# SAM_D21_DevBoard.net
KiCad netlist of a schematic drawn in EAGLE
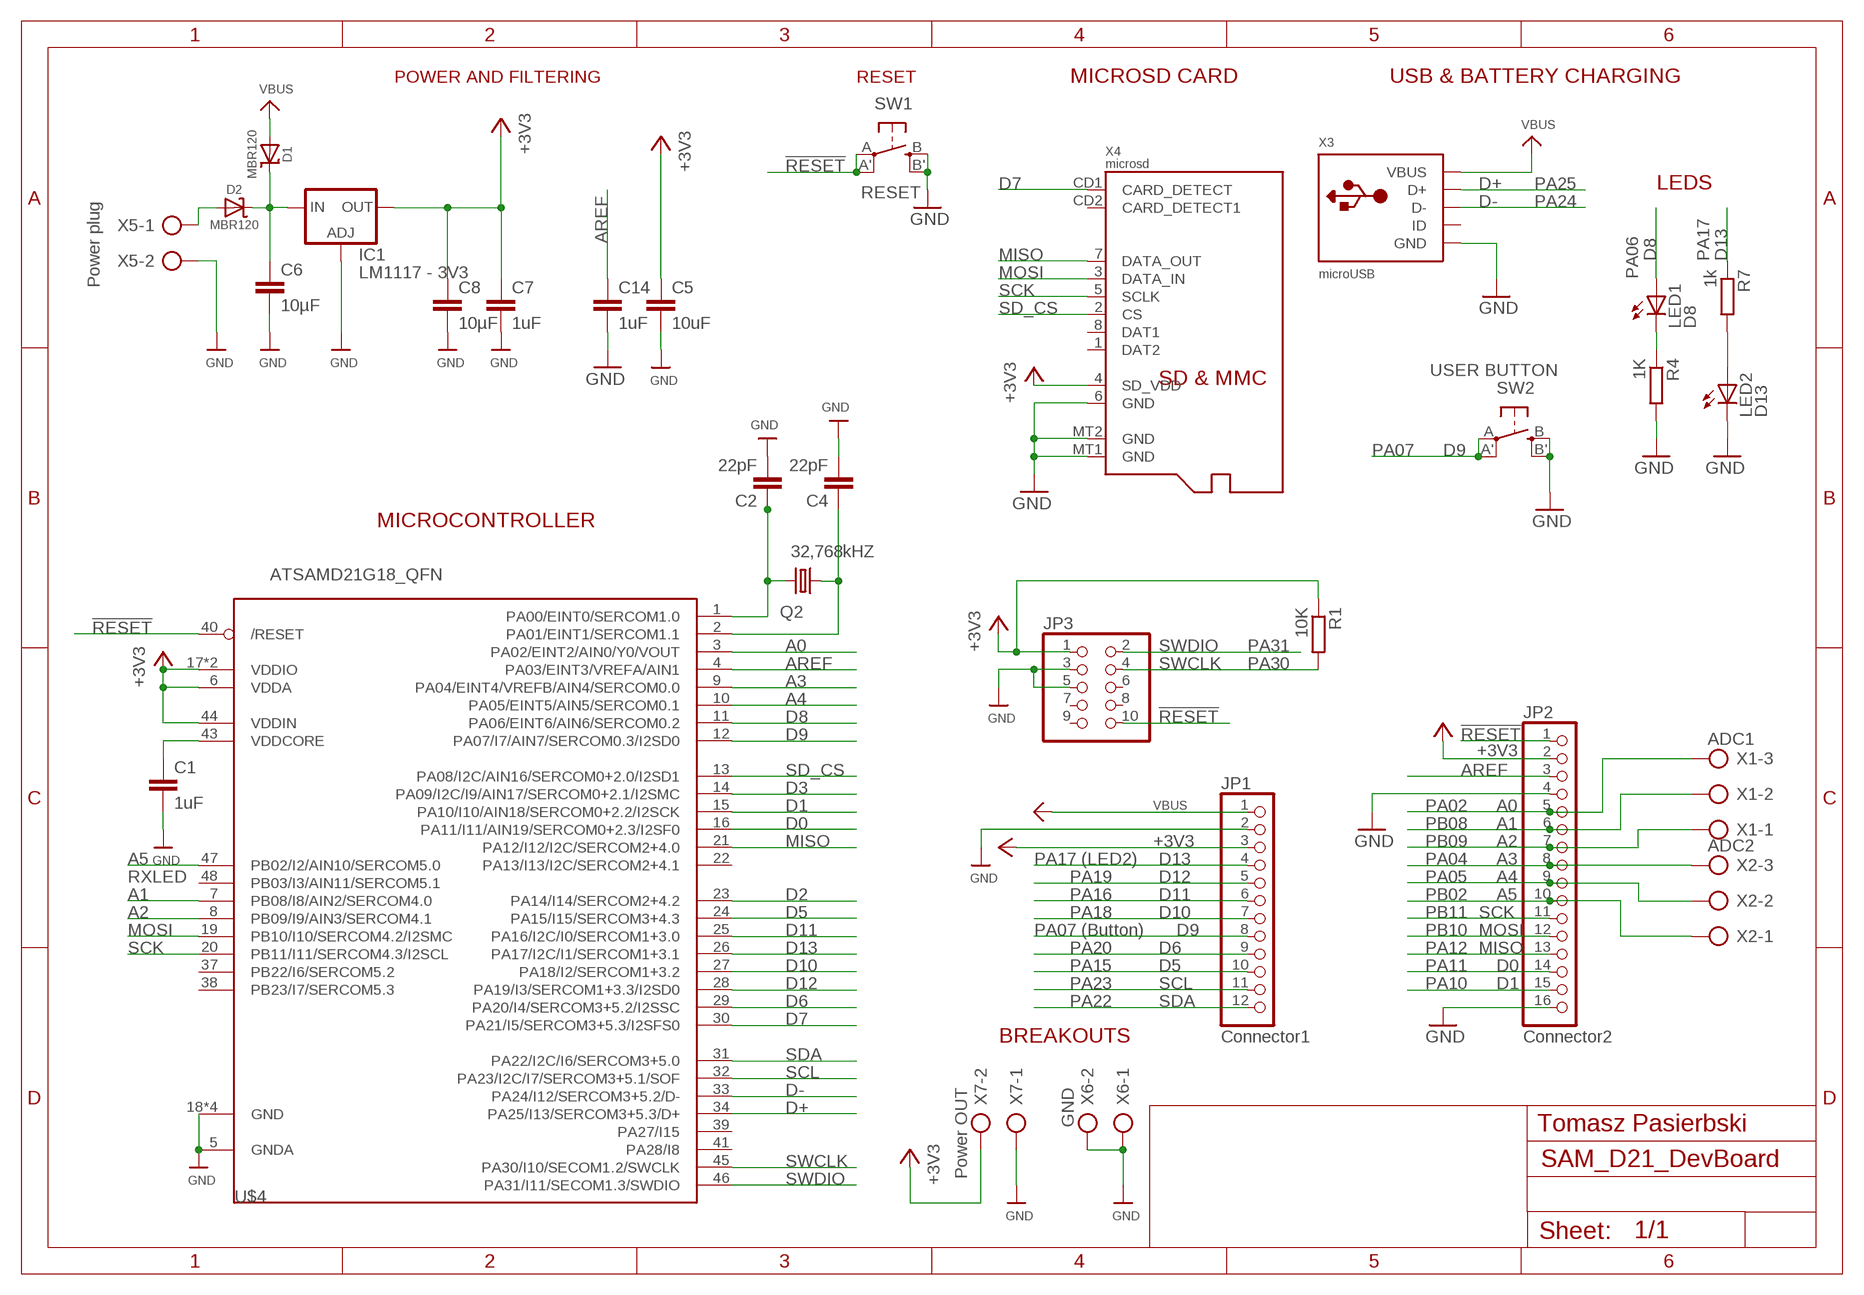
[diagram p0: schematic, sheet 1]

(export (version "E")
  (design (tool "Eeschema 10.0.6"))
  (components
    (comp (ref "C1")
      (value "1uF")
      (footprint "eagle-import:C1206")
      (libsource (lib "eagle-import") (part "C-EUC1206"))
    )
    (comp (ref "C2")
      (value "22pF")
      (footprint "eagle-import:C1206")
      (libsource (lib "eagle-import") (part "C-EUC1206"))
    )
    (comp (ref "C4")
      (value "22pF")
      (footprint "eagle-import:C1206")
      (libsource (lib "eagle-import") (part "C-EUC1206"))
    )
    (comp (ref "C5")
      (value "10uF")
      (footprint "eagle-import:C1206")
      (libsource (lib "eagle-import") (part "C-EUC1206"))
    )
    (comp (ref "C6")
      (value "10µF")
      (footprint "eagle-import:C1206")
      (libsource (lib "eagle-import") (part "C-EUC1206"))
    )
    (comp (ref "C7")
      (value "1uF")
      (footprint "eagle-import:C1206")
      (libsource (lib "eagle-import") (part "C-EUC1206"))
    )
    (comp (ref "C8")
      (value "10µF")
      (footprint "eagle-import:C1206")
      (libsource (lib "eagle-import") (part "C-EUC1206"))
    )
    (comp (ref "C14")
      (value "1uF")
      (footprint "eagle-import:C1206")
      (libsource (lib "eagle-import") (part "C-EUC1206"))
    )
    (comp (ref "D1")
      (value "MBR120")
      (footprint "eagle-import:SOD-123")
      (libsource (lib "eagle-import") (part "DIODE-SCHOTTKYSOD-123"))
    )
    (comp (ref "D2")
      (value "MBR120")
      (footprint "eagle-import:SOD-123")
      (libsource (lib "eagle-import") (part "DIODE-SCHOTTKYSOD-123"))
    )
    (comp (ref "IC1")
      (value "LM1117 - 3V3")
      (footprint "eagle-import:SOT223")
      (libsource (lib "eagle-import") (part "LD117A?S33TR"))
    )
    (comp (ref "JP1")
      (value "Connector1")
      (footprint "eagle-import:1X12")
      (libsource (lib "eagle-import") (part "PINHD-1X12"))
    )
    (comp (ref "JP2")
      (value "Connector2")
      (footprint "eagle-import:1X16")
      (libsource (lib "eagle-import") (part "PINHD-1X16"))
    )
    (comp (ref "JP3")
      (value "PINHD-2X5")
      (footprint "eagle-import:2X05")
      (libsource (lib "eagle-import") (part "PINHD-2X5"))
    )
    (comp (ref "LED1")
      (value "D8")
      (footprint "eagle-import:1206")
      (libsource (lib "eagle-import") (part "LEDSMT1206"))
    )
    (comp (ref "LED2")
      (value "D13")
      (footprint "eagle-import:1206")
      (libsource (lib "eagle-import") (part "LEDSMT1206"))
    )
    (comp (ref "Q2")
      (value "32,768kHZ")
      (footprint "eagle-import:HC49UP")
      (libsource (lib "eagle-import") (part "CRYSTALHC49UP"))
    )
    (comp (ref "R1")
      (value "10K")
      (footprint "eagle-import:M1206")
      (libsource (lib "eagle-import") (part "R-EU_M1206"))
    )
    (comp (ref "R4")
      (value "1K")
      (footprint "eagle-import:M1206")
      (libsource (lib "eagle-import") (part "R-EU_M1206"))
    )
    (comp (ref "R7")
      (value "1k")
      (footprint "eagle-import:M1206")
      (libsource (lib "eagle-import") (part "R-EU_M1206"))
    )
    (comp (ref "SW1")
      (value "RESET")
      (footprint "eagle-import:EVQ-Q2")
      (libsource (lib "eagle-import") (part "SPST_TACT-EVQQ2"))
    )
    (comp (ref "SW2")
      (value "USER BUTTON")
      (footprint "eagle-import:EVQ-Q2")
      (libsource (lib "eagle-import") (part "SPST_TACT-EVQQ2"))
    )
    (comp (ref "U$4")
      (value "ATSAMD21G18_QFN")
      (footprint "eagle-import:TQFN48_7MM")
      (libsource (lib "eagle-import") (part "ATSAMD21J_QFN"))
    )
    (comp (ref "X1")
      (value "ADC1")
      (footprint "eagle-import:AK300_3")
      (libsource (lib "eagle-import") (part "AK300/3"))
    )
    (comp (ref "X2")
      (value "ADC2")
      (footprint "eagle-import:AK300_3")
      (libsource (lib "eagle-import") (part "AK300/3"))
    )
    (comp (ref "X3")
      (value "microUSB")
      (footprint "eagle-import:4UCONN_20329_V2")
      (libsource (lib "eagle-import") (part "USB_MICRO_20329_V2"))
    )
    (comp (ref "X4")
      (value "microsd")
      (footprint "eagle-import:MICROSD")
      (libsource (lib "eagle-import") (part "MICROSD"))
    )
    (comp (ref "X5")
      (value "Power plug")
      (footprint "eagle-import:AK300_2")
      (libsource (lib "eagle-import") (part "AK300/2"))
    )
    (comp (ref "X6")
      (value "GND")
      (footprint "eagle-import:AK300_2")
      (libsource (lib "eagle-import") (part "AK300/2"))
    )
    (comp (ref "X7")
      (value "Power OUT")
      (footprint "eagle-import:AK300_2")
      (libsource (lib "eagle-import") (part "AK300/2"))
    )
  )
  (nets
    (net (code "1") (name "+3V3") (class "Default")
      (node (ref "C5") (pin "1") (pinfunction "1_1") (pintype "passive"))
      (node (ref "C7") (pin "1") (pinfunction "1_1") (pintype "passive"))
      (node (ref "C8") (pin "1") (pinfunction "1_1") (pintype "passive"))
      (node (ref "IC1") (pin "4") (pinfunction "OUT_4") (pintype "passive"))
      (node (ref "JP1") (pin "3") (pinfunction "3_3") (pintype "passive"))
      (node (ref "JP2") (pin "2") (pinfunction "2_2") (pintype "passive"))
      (node (ref "JP3") (pin "1") (pinfunction "1_1") (pintype "passive"))
      (node (ref "R1") (pin "1") (pinfunction "1_1") (pintype "passive"))
      (node (ref "U$4") (pin "17") (pinfunction "VDDIO_17") (pintype "power_in"))
      (node (ref "U$4") (pin "36") (pinfunction "VDDIO_36") (pintype "power_in"))
      (node (ref "U$4") (pin "44") (pinfunction "VDDIN_44") (pintype "power_in"))
      (node (ref "U$4") (pin "6") (pinfunction "VDDA_6") (pintype "power_in"))
      (node (ref "X4") (pin "4") (pinfunction "SD_VDD_4") (pintype "power_in"))
      (node (ref "X7") (pin "2") (pinfunction "KL_2") (pintype "passive"))
    )
    (net (code "2") (name "/A0") (class "Default")
      (node (ref "JP2") (pin "5") (pinfunction "5_5") (pintype "passive"))
      (node (ref "U$4") (pin "3") (pinfunction "PA02/EINT2/AIN0/Y0/VOUT_3") (pintype "bidirectional"))
      (node (ref "X1") (pin "3") (pinfunction "KL_3") (pintype "passive"))
    )
    (net (code "3") (name "/A1") (class "Default")
      (node (ref "JP2") (pin "6") (pinfunction "6_6") (pintype "passive"))
      (node (ref "U$4") (pin "7") (pinfunction "PB08/I8/AIN2/SERCOM4.0_7") (pintype "bidirectional"))
      (node (ref "X1") (pin "2") (pinfunction "KL_2") (pintype "passive"))
    )
    (net (code "4") (name "/A2") (class "Default")
      (node (ref "JP2") (pin "7") (pinfunction "7_7") (pintype "passive"))
      (node (ref "U$4") (pin "8") (pinfunction "PB09/I9/AIN3/SERCOM4.1_8") (pintype "bidirectional"))
      (node (ref "X1") (pin "1") (pinfunction "KL_1") (pintype "passive"))
    )
    (net (code "5") (name "/A3") (class "Default")
      (node (ref "JP2") (pin "8") (pinfunction "8_8") (pintype "passive"))
      (node (ref "U$4") (pin "9") (pinfunction "PA04/EINT4/VREFB/AIN4/SERCOM0.0_9") (pintype "bidirectional"))
      (node (ref "X2") (pin "3") (pinfunction "KL_3") (pintype "passive"))
    )
    (net (code "6") (name "/A4") (class "Default")
      (node (ref "JP2") (pin "9") (pinfunction "9_9") (pintype "passive"))
      (node (ref "U$4") (pin "10") (pinfunction "PA05/EINT5/AIN5/SERCOM0.1_10") (pintype "bidirectional"))
      (node (ref "X2") (pin "2") (pinfunction "KL_2") (pintype "passive"))
    )
    (net (code "7") (name "/A5") (class "Default")
      (node (ref "JP2") (pin "10") (pinfunction "10_10") (pintype "passive"))
      (node (ref "U$4") (pin "47") (pinfunction "PB02/I2/AIN10/SERCOM5.0_47") (pintype "bidirectional"))
      (node (ref "X2") (pin "1") (pinfunction "KL_1") (pintype "passive"))
    )
    (net (code "8") (name "/AREF") (class "Default")
      (node (ref "C14") (pin "1") (pinfunction "1_1") (pintype "passive"))
      (node (ref "JP2") (pin "3") (pinfunction "3_3") (pintype "passive"))
      (node (ref "U$4") (pin "4") (pinfunction "PA03/EINT3/VREFA/AIN1_4") (pintype "bidirectional"))
    )
    (net (code "9") (name "/D+") (class "Default")
      (node (ref "U$4") (pin "34") (pinfunction "PA25/I13/SERCOM3+5.3/D+_34") (pintype "bidirectional"))
      (node (ref "X3") (pin "D+") (pinfunction "D+_D+") (pintype "bidirectional"))
    )
    (net (code "10") (name "/D-") (class "Default")
      (node (ref "U$4") (pin "33") (pinfunction "PA24/I12/SERCOM3+5.2/D-_33") (pintype "bidirectional"))
      (node (ref "X3") (pin "D-") (pinfunction "D-_D-") (pintype "bidirectional"))
    )
    (net (code "11") (name "/D0") (class "Default")
      (node (ref "JP2") (pin "14") (pinfunction "14_14") (pintype "passive"))
      (node (ref "U$4") (pin "16") (pinfunction "PA11/I11/AIN19/SERCOM0+2.3/I2SF0_16") (pintype "bidirectional"))
    )
    (net (code "12") (name "/D1") (class "Default")
      (node (ref "JP2") (pin "15") (pinfunction "15_15") (pintype "passive"))
      (node (ref "U$4") (pin "15") (pinfunction "PA10/I10/AIN18/SERCOM0+2.2/I2SCK_15") (pintype "bidirectional"))
    )
    (net (code "13") (name "/D2") (class "Default")
      (node (ref "U$4") (pin "23") (pinfunction "PA14/I14/SERCOM2+4.2_23") (pintype "bidirectional"))
    )
    (net (code "14") (name "/D3") (class "Default")
      (node (ref "U$4") (pin "14") (pinfunction "PA09/I2C/I9/AIN17/SERCOM0+2.1/I2SMC_14") (pintype "bidirectional"))
    )
    (net (code "15") (name "/D5") (class "Default")
      (node (ref "JP1") (pin "10") (pinfunction "10_10") (pintype "passive"))
      (node (ref "U$4") (pin "24") (pinfunction "PA15/I15/SERCOM3+4.3_24") (pintype "bidirectional"))
    )
    (net (code "16") (name "/D6") (class "Default")
      (node (ref "JP1") (pin "9") (pinfunction "9_9") (pintype "passive"))
      (node (ref "U$4") (pin "29") (pinfunction "PA20/I4/SERCOM3+5.2/I2SSC_29") (pintype "bidirectional"))
    )
    (net (code "17") (name "/D7") (class "Default")
      (node (ref "U$4") (pin "30") (pinfunction "PA21/I5/SERCOM3+5.3/I2SFS0_30") (pintype "bidirectional"))
      (node (ref "X4") (pin "CD1") (pinfunction "CARD_DETECT_CD1") (pintype "passive"))
    )
    (net (code "18") (name "/D8") (class "Default")
      (node (ref "LED1") (pin "A") (pinfunction "A_A") (pintype "passive"))
      (node (ref "U$4") (pin "11") (pinfunction "PA06/EINT6/AIN6/SERCOM0.2_11") (pintype "bidirectional"))
    )
    (net (code "19") (name "/D9") (class "Default")
      (node (ref "JP1") (pin "8") (pinfunction "8_8") (pintype "passive"))
      (node (ref "SW2") (pin "A") (pinfunction "P_A") (pintype "passive"))
      (node (ref "SW2") (pin "A'") (pinfunction "P1_A'") (pintype "passive"))
      (node (ref "U$4") (pin "12") (pinfunction "PA07/I7/AIN7/SERCOM0.3/I2SD0_12") (pintype "bidirectional"))
    )
    (net (code "20") (name "/D10") (class "Default")
      (node (ref "JP1") (pin "7") (pinfunction "7_7") (pintype "passive"))
      (node (ref "U$4") (pin "27") (pinfunction "PA18/I2/SERCOM1+3.2_27") (pintype "bidirectional"))
    )
    (net (code "21") (name "/D11") (class "Default")
      (node (ref "JP1") (pin "6") (pinfunction "6_6") (pintype "passive"))
      (node (ref "U$4") (pin "25") (pinfunction "PA16/I2C/I0/SERCOM1+3.0_25") (pintype "bidirectional"))
    )
    (net (code "22") (name "/D12") (class "Default")
      (node (ref "JP1") (pin "5") (pinfunction "5_5") (pintype "passive"))
      (node (ref "U$4") (pin "28") (pinfunction "PA19/I3/SERCOM1+3.3/I2SD0_28") (pintype "bidirectional"))
    )
    (net (code "23") (name "/D13") (class "Default")
      (node (ref "JP1") (pin "4") (pinfunction "4_4") (pintype "passive"))
      (node (ref "R7") (pin "1") (pinfunction "1_1") (pintype "passive"))
      (node (ref "U$4") (pin "26") (pinfunction "PA17/I2C/I1/SERCOM1+3.1_26") (pintype "bidirectional"))
    )
    (net (code "24") (name "/MISO") (class "Default")
      (node (ref "JP2") (pin "13") (pinfunction "13_13") (pintype "passive"))
      (node (ref "U$4") (pin "21") (pinfunction "PA12/I12/I2C/SERCOM2+4.0_21") (pintype "bidirectional"))
      (node (ref "X4") (pin "7") (pinfunction "DATA_OUT_7") (pintype "output"))
    )
    (net (code "25") (name "/MOSI") (class "Default")
      (node (ref "JP2") (pin "12") (pinfunction "12_12") (pintype "passive"))
      (node (ref "U$4") (pin "19") (pinfunction "PB10/I10/SERCOM4.2/I2SMC_19") (pintype "bidirectional"))
      (node (ref "X4") (pin "3") (pinfunction "DATA_IN_3") (pintype "input"))
    )
    (net (code "26") (name "/SCK") (class "Default")
      (node (ref "JP2") (pin "11") (pinfunction "11_11") (pintype "passive"))
      (node (ref "U$4") (pin "20") (pinfunction "PB11/I11/SERCOM4.3/I2SCL_20") (pintype "bidirectional"))
      (node (ref "X4") (pin "5") (pinfunction "SCLK_5") (pintype "input"))
    )
    (net (code "27") (name "/SCL") (class "Default")
      (node (ref "JP1") (pin "11") (pinfunction "11_11") (pintype "passive"))
      (node (ref "U$4") (pin "32") (pinfunction "PA23/I2C/I7/SERCOM3+5.1/SOF_32") (pintype "bidirectional"))
    )
    (net (code "28") (name "/SDA") (class "Default")
      (node (ref "JP1") (pin "12") (pinfunction "12_12") (pintype "passive"))
      (node (ref "U$4") (pin "31") (pinfunction "PA22/I2C/I6/SERCOM3+5.0_31") (pintype "bidirectional"))
    )
    (net (code "29") (name "/SD_CS") (class "Default")
      (node (ref "U$4") (pin "13") (pinfunction "PA08/I2C/AIN16/SERCOM0+2.0/I2SD1_13") (pintype "bidirectional"))
      (node (ref "X4") (pin "2") (pinfunction "CS_2") (pintype "input"))
    )
    (net (code "30") (name "/SWCLK") (class "Default")
      (node (ref "JP3") (pin "4") (pinfunction "4_4") (pintype "passive"))
      (node (ref "R1") (pin "2") (pinfunction "2_2") (pintype "passive"))
      (node (ref "U$4") (pin "45") (pinfunction "PA30/I10/SECOM1.2/SWCLK_45") (pintype "bidirectional"))
    )
    (net (code "31") (name "/SWDIO") (class "Default")
      (node (ref "JP3") (pin "2") (pinfunction "2_2") (pintype "passive"))
      (node (ref "U$4") (pin "46") (pinfunction "PA31/I11/SECOM1.3/SWDIO_46") (pintype "bidirectional"))
    )
    (net (code "32") (name "/~{RESET}") (class "Default")
      (node (ref "JP2") (pin "1") (pinfunction "1_1") (pintype "passive"))
      (node (ref "JP3") (pin "10") (pinfunction "10_10") (pintype "passive"))
      (node (ref "SW1") (pin "A") (pinfunction "P_A") (pintype "passive"))
      (node (ref "SW1") (pin "A'") (pinfunction "P1_A'") (pintype "passive"))
      (node (ref "U$4") (pin "40") (pinfunction "/RESET_40") (pintype "bidirectional"))
    )
    (net (code "33") (name "GND") (class "Default")
      (node (ref "C1") (pin "2") (pinfunction "2_2") (pintype "passive"))
      (node (ref "C14") (pin "2") (pinfunction "2_2") (pintype "passive"))
      (node (ref "C2") (pin "2") (pinfunction "2_2") (pintype "passive"))
      (node (ref "C4") (pin "2") (pinfunction "2_2") (pintype "passive"))
      (node (ref "C5") (pin "2") (pinfunction "2_2") (pintype "passive"))
      (node (ref "C6") (pin "2") (pinfunction "2_2") (pintype "passive"))
      (node (ref "C7") (pin "2") (pinfunction "2_2") (pintype "passive"))
      (node (ref "C8") (pin "2") (pinfunction "2_2") (pintype "passive"))
      (node (ref "IC1") (pin "1") (pinfunction "ADJ_1") (pintype "input"))
      (node (ref "JP1") (pin "2") (pinfunction "2_2") (pintype "passive"))
      (node (ref "JP2") (pin "16") (pinfunction "16_16") (pintype "passive"))
      (node (ref "JP2") (pin "4") (pinfunction "4_4") (pintype "passive"))
      (node (ref "JP3") (pin "3") (pinfunction "3_3") (pintype "passive"))
      (node (ref "JP3") (pin "5") (pinfunction "5_5") (pintype "passive"))
      (node (ref "LED2") (pin "C") (pinfunction "C_C") (pintype "passive"))
      (node (ref "R4") (pin "2") (pinfunction "2_2") (pintype "passive"))
      (node (ref "SW1") (pin "B") (pinfunction "S_B") (pintype "passive"))
      (node (ref "SW1") (pin "B'") (pinfunction "S1_B'") (pintype "passive"))
      (node (ref "SW2") (pin "B") (pinfunction "S_B") (pintype "passive"))
      (node (ref "SW2") (pin "B'") (pinfunction "S1_B'") (pintype "passive"))
      (node (ref "U$4") (pin "18") (pinfunction "GND_18") (pintype "power_in"))
      (node (ref "U$4") (pin "35") (pinfunction "GND_35") (pintype "power_in"))
      (node (ref "U$4") (pin "42") (pinfunction "GND_42") (pintype "power_in"))
      (node (ref "U$4") (pin "5") (pinfunction "GNDA_5") (pintype "power_in"))
      (node (ref "U$4") (pin "THERMAL") (pinfunction "GND_THERMAL") (pintype "power_in"))
      (node (ref "X3") (pin "BASE@1") (pinfunction "GND_BASE@1") (pintype "power_in"))
      (node (ref "X3") (pin "BASE@2") (pinfunction "GND_BASE@2") (pintype "power_in"))
      (node (ref "X3") (pin "GND") (pinfunction "GND_GND") (pintype "power_in"))
      (node (ref "X3") (pin "SPRT@1") (pinfunction "GND_SPRT@1") (pintype "power_in"))
      (node (ref "X3") (pin "SPRT@2") (pinfunction "GND_SPRT@2") (pintype "power_in"))
      (node (ref "X3") (pin "SPRT@3") (pinfunction "GND_SPRT@3") (pintype "power_in"))
      (node (ref "X3") (pin "SPRT@4") (pinfunction "GND_SPRT@4") (pintype "power_in"))
      (node (ref "X4") (pin "6") (pinfunction "GND_6") (pintype "power_in"))
      (node (ref "X4") (pin "MT1") (pinfunction "GND_MT1") (pintype "power_in"))
      (node (ref "X4") (pin "MT2") (pinfunction "GND_MT2") (pintype "power_in"))
      (node (ref "X5") (pin "2") (pinfunction "KL_2") (pintype "passive"))
      (node (ref "X6") (pin "1") (pinfunction "KL_1") (pintype "passive"))
      (node (ref "X6") (pin "2") (pinfunction "KL_2") (pintype "passive"))
      (node (ref "X7") (pin "1") (pinfunction "KL_1") (pintype "passive"))
    )
    (net (code "34") (name "Net-(IC1-IN)") (class "Default")
      (node (ref "C6") (pin "1") (pinfunction "1_1") (pintype "passive"))
      (node (ref "D1") (pin "C") (pinfunction "C_C") (pintype "passive"))
      (node (ref "D2") (pin "C") (pinfunction "C_C") (pintype "passive"))
      (node (ref "IC1") (pin "3") (pinfunction "IN_3") (pintype "input"))
    )
    (net (code "35") (name "Net-(LED1-PadC)") (class "Default")
      (node (ref "LED1") (pin "C") (pinfunction "C_C") (pintype "passive"))
      (node (ref "R4") (pin "1") (pinfunction "1_1") (pintype "passive"))
    )
    (net (code "36") (name "Net-(LED2-PadA)") (class "Default")
      (node (ref "LED2") (pin "A") (pinfunction "A_A") (pintype "passive"))
      (node (ref "R7") (pin "2") (pinfunction "2_2") (pintype "passive"))
    )
    (net (code "37") (name "Net-(U$4-PA00{slash}EINT0{slash}SERCOM1.0)") (class "Default")
      (node (ref "C2") (pin "1") (pinfunction "1_1") (pintype "passive"))
      (node (ref "Q2") (pin "2") (pinfunction "2_2") (pintype "passive"))
      (node (ref "U$4") (pin "1") (pinfunction "PA00/EINT0/SERCOM1.0_1") (pintype "bidirectional"))
    )
    (net (code "38") (name "Net-(U$4-PA01{slash}EINT1{slash}SERCOM1.1)") (class "Default")
      (node (ref "C4") (pin "1") (pinfunction "1_1") (pintype "passive"))
      (node (ref "Q2") (pin "1") (pinfunction "1_1") (pintype "passive"))
      (node (ref "U$4") (pin "2") (pinfunction "PA01/EINT1/SERCOM1.1_2") (pintype "bidirectional"))
    )
    (net (code "39") (name "Net-(U$4-VDDCORE)") (class "Default")
      (node (ref "C1") (pin "1") (pinfunction "1_1") (pintype "passive"))
      (node (ref "U$4") (pin "43") (pinfunction "VDDCORE_43") (pintype "power_in"))
    )
    (net (code "40") (name "Net-(X5A-KL)") (class "Default")
      (node (ref "D2") (pin "A") (pinfunction "A_A") (pintype "passive"))
      (node (ref "X5") (pin "1") (pinfunction "KL_1") (pintype "passive"))
    )
    (net (code "41") (name "VBUS") (class "Default")
      (node (ref "D1") (pin "A") (pinfunction "A_A") (pintype "passive"))
      (node (ref "JP1") (pin "1") (pinfunction "1_1") (pintype "passive"))
      (node (ref "X3") (pin "VBUS") (pinfunction "VBUS_VBUS") (pintype "power_in"))
    )
    (net (code "42") (name "unconnected-(JP3-Pad6)") (class "Default")
      (node (ref "JP3") (pin "6") (pinfunction "6_6") (pintype "passive"))
    )
    (net (code "43") (name "unconnected-(JP3-Pad7)") (class "Default")
      (node (ref "JP3") (pin "7") (pinfunction "7_7") (pintype "passive"))
    )
    (net (code "44") (name "unconnected-(JP3-Pad8)") (class "Default")
      (node (ref "JP3") (pin "8") (pinfunction "8_8") (pintype "passive"))
    )
    (net (code "45") (name "unconnected-(JP3-Pad9)") (class "Default")
      (node (ref "JP3") (pin "9") (pinfunction "9_9") (pintype "passive"))
    )
    (net (code "46") (name "unconnected-(U$4-PA13{slash}I13{slash}I2C{slash}SERCOM2+4.1-Pad22)") (class "Default")
      (node (ref "U$4") (pin "22") (pinfunction "PA13/I13/I2C/SERCOM2+4.1_22") (pintype "bidirectional"))
    )
    (net (code "47") (name "unconnected-(U$4-PA27{slash}I15-Pad39)") (class "Default")
      (node (ref "U$4") (pin "39") (pinfunction "PA27/I15_39") (pintype "bidirectional"))
    )
    (net (code "48") (name "unconnected-(U$4-PA28{slash}I8-Pad41)") (class "Default")
      (node (ref "U$4") (pin "41") (pinfunction "PA28/I8_41") (pintype "bidirectional"))
    )
    (net (code "49") (name "unconnected-(U$4-PB03{slash}I3{slash}AIN11{slash}SERCOM5.1-Pad48)") (class "Default")
      (node (ref "U$4") (pin "48") (pinfunction "PB03/I3/AIN11/SERCOM5.1_48") (pintype "bidirectional"))
    )
    (net (code "50") (name "unconnected-(U$4-PB22{slash}I6{slash}SERCOM5.2-Pad37)") (class "Default")
      (node (ref "U$4") (pin "37") (pinfunction "PB22/I6/SERCOM5.2_37") (pintype "bidirectional"))
    )
    (net (code "51") (name "unconnected-(U$4-PB23{slash}I7{slash}SERCOM5.3-Pad38)") (class "Default")
      (node (ref "U$4") (pin "38") (pinfunction "PB23/I7/SERCOM5.3_38") (pintype "bidirectional"))
    )
    (net (code "52") (name "unconnected-(X3-PadID)") (class "Default")
      (node (ref "X3") (pin "ID") (pinfunction "ID_ID") (pintype "bidirectional"))
    )
    (net (code "53") (name "unconnected-(X4-CARD_DETECT1-PadCD2)") (class "Default")
      (node (ref "X4") (pin "CD2") (pinfunction "CARD_DETECT1_CD2") (pintype "passive"))
    )
    (net (code "54") (name "unconnected-(X4-DAT1-Pad8)") (class "Default")
      (node (ref "X4") (pin "8") (pinfunction "DAT1_8") (pintype "bidirectional"))
    )
    (net (code "55") (name "unconnected-(X4-DAT2-Pad1)") (class "Default")
      (node (ref "X4") (pin "1") (pinfunction "DAT2_1") (pintype "bidirectional"))
    )
  )
)
